# Schematic_pH_CAN.net
KiCad netlist of a schematic drawn in Altium Designer
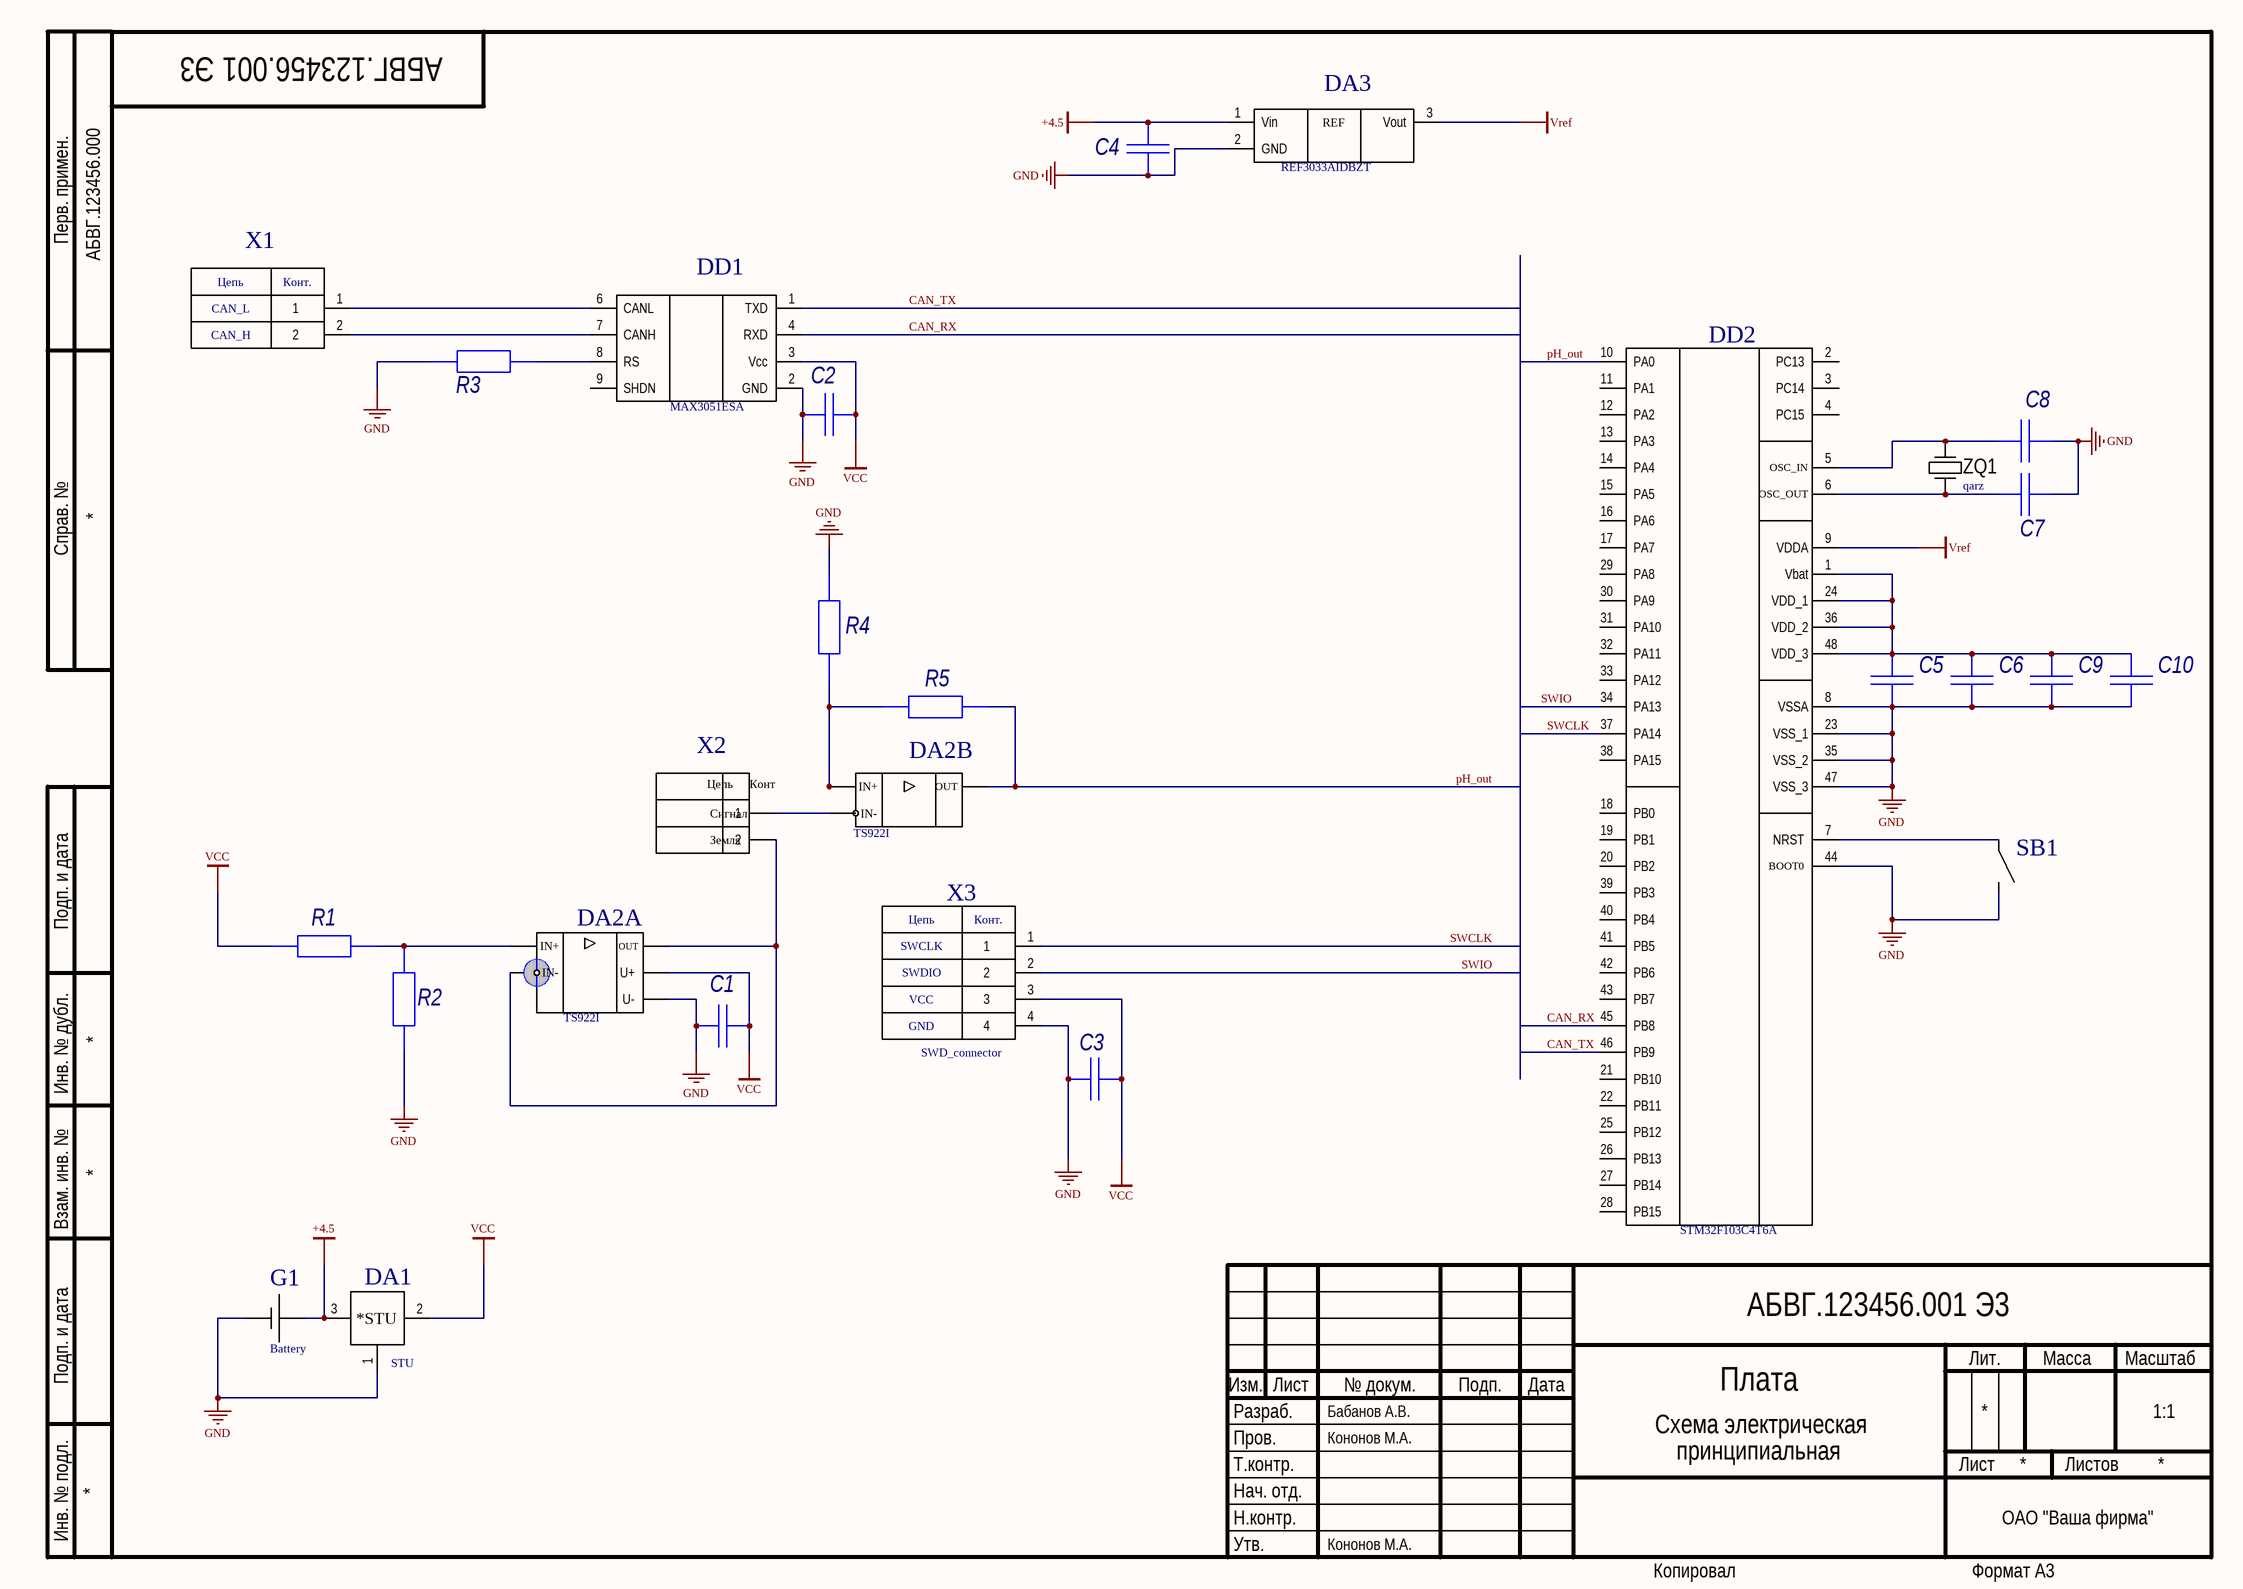
[diagram p0: Schematic_pH_CAN.SchDoc]

(export (version "E")
  (design (tool "Eeschema 10.0.6"))
  (components
    (comp (ref "C1")
      (value "Capacitor")
      (footprint "StandardCase:CAP: 0805")
      (fields (field (name "PUBLISHER") "Andrew Danich"))
      (libsource (lib "Schlib1") (part "Capacitor"))
    )
    (comp (ref "C2")
      (value "Capacitor")
      (footprint "StandardCase:CAP: 0805")
      (fields (field (name "PUBLISHER") "Andrew Danich"))
      (libsource (lib "Schlib1") (part "Capacitor"))
    )
    (comp (ref "C3")
      (value "Capacitor")
      (footprint "StandardCase:CAP: 0805")
      (fields (field (name "PUBLISHER") "Andrew Danich"))
      (libsource (lib "Schlib1") (part "Capacitor"))
    )
    (comp (ref "C4")
      (value "Capacitor")
      (footprint "StandardCase:CAP: 0805")
      (fields (field (name "PUBLISHER") "Andrew Danich"))
      (libsource (lib "Schlib1") (part "Capacitor"))
    )
    (comp (ref "C5")
      (value "Capacitor")
      (footprint "StandardCase:CAP: 0805")
      (fields (field (name "PUBLISHER") "Andrew Danich"))
      (libsource (lib "Schlib1") (part "Capacitor"))
    )
    (comp (ref "C6")
      (value "Capacitor")
      (footprint "StandardCase:CAP: 0805")
      (fields (field (name "PUBLISHER") "Andrew Danich"))
      (libsource (lib "Schlib1") (part "Capacitor"))
    )
    (comp (ref "C7")
      (value "Capacitor")
      (footprint "StandardCase:CAP: 0805")
      (fields (field (name "PUBLISHER") "Andrew Danich"))
      (libsource (lib "Schlib1") (part "Capacitor"))
    )
    (comp (ref "C8")
      (value "Capacitor")
      (footprint "StandardCase:CAP: 0805")
      (fields (field (name "PUBLISHER") "Andrew Danich"))
      (libsource (lib "Schlib1") (part "Capacitor"))
    )
    (comp (ref "C9")
      (value "Capacitor")
      (footprint "StandardCase:CAP: 0805")
      (fields (field (name "PUBLISHER") "Andrew Danich"))
      (libsource (lib "Schlib1") (part "Capacitor"))
    )
    (comp (ref "C10")
      (value "Capacitor")
      (footprint "StandardCase:CAP: 0805")
      (fields (field (name "PUBLISHER") "Andrew Danich"))
      (libsource (lib "Schlib1") (part "Capacitor"))
    )
    (comp (ref "DA1")
      (value "STU")
      (footprint "SOT223")
      (description "Стабилизатор напряжения")
      (libsource (lib "Schlib1") (part "STU"))
    )
    (comp (ref "DA2")
      (value "TS922I")
      (footprint "8-SO")
      (description "OPAMP 2 channel")
      (libsource (lib "Schlib1") (part "TS922I"))
    )
    (comp (ref "DA3")
      (value "REF3033AIDBZT")
      (description "ИОН 3.3 В")
      (libsource (lib "Schlib1") (part "REF3033AIDBZT"))
    )
    (comp (ref "DD1") (value "MAX3051ESA") (libsource (lib "Schlib1") (part "MAX3051ESA")))
    (comp (ref "DD2")
      (value "STM32F103C4T6A")
      (description "МК")
      (libsource (lib "Schlib1") (part "STM32F103C4T6A"))
    )
    (comp (ref "G1") (value "Battery") (footprint "VCC Pad") (libsource (lib "Schlib1") (part "Battery")))
    (comp (ref "R1")
      (value "Resistor")
      (footprint "RES: 0805")
      (fields (field (name "PUBLISHER") "Andrew Danich"))
      (libsource (lib "Schlib1") (part "Resistor"))
    )
    (comp (ref "R2")
      (value "Resistor")
      (footprint "RES: 0805")
      (fields (field (name "PUBLISHER") "Andrew Danich"))
      (libsource (lib "Schlib1") (part "Resistor"))
    )
    (comp (ref "R3")
      (value "Resistor")
      (footprint "RES: 0805")
      (fields (field (name "PUBLISHER") "Andrew Danich"))
      (libsource (lib "Schlib1") (part "Resistor"))
    )
    (comp (ref "R4")
      (value "Resistor")
      (footprint "RES: 0805")
      (fields (field (name "PUBLISHER") "Andrew Danich"))
      (libsource (lib "Schlib1") (part "Resistor"))
    )
    (comp (ref "R5")
      (value "Resistor")
      (footprint "RES: 0805")
      (fields (field (name "PUBLISHER") "Andrew Danich"))
      (libsource (lib "Schlib1") (part "Resistor"))
    )
    (comp (ref "SB1")
      (value "KLS7-TS6601-7")
      (footprint "KLS7-TS6601-7")
      (libsource (lib "Schlib1") (part "KLS7-TS6601-7"))
    )
    (comp (ref "X1")
      (value "CAN_L/CAN_H")
      (footprint "Клеммная колодка")
      (libsource (lib "Schlib1") (part "CAN_L/CAN_H"))
    )
    (comp (ref "X2") (value "BNC") (footprint "BNC") (libsource (lib "Schlib1") (part "BNC")))
    (comp (ref "X3")
      (value "SWD_connector")
      (footprint "PLS-4")
      (libsource (lib "Schlib1") (part "SWD_connector"))
    )
    (comp (ref "ZQ1")
      (value "qarz")
      (footprint "StandardCase:qarz")
      (libsource (lib "Schlib1") (part "qarz"))
    )
  )
  (nets
    (net (code "1") (name "+4.5") (class "Default")
      (node (ref "C4") (pin "2") (pinfunction "2_2") (pintype "passive"))
      (node (ref "DA1") (pin "3") (pinfunction "3_3") (pintype "passive"))
      (node (ref "DA3") (pin "1") (pinfunction "Vin_1") (pintype "passive"))
      (node (ref "G1") (pin "1") (pinfunction "1_1") (pintype "passive"))
    )
    (net (code "2") (name "/CAN_RX") (class "Default")
      (node (ref "DA2") (pin "7") (pinfunction "OUT_7") (pintype "passive"))
      (node (ref "DD1") (pin "4") (pinfunction "RXD_4") (pintype "passive"))
      (node (ref "DD2") (pin "10") (pinfunction "PA0_10") (pintype "passive"))
      (node (ref "DD2") (pin "45") (pinfunction "PB8_45") (pintype "passive"))
      (node (ref "R5") (pin "1") (pinfunction "1_1") (pintype "passive"))
    )
    (net (code "3") (name "/CAN_TX") (class "Default")
      (node (ref "DD1") (pin "1") (pinfunction "TXD_1") (pintype "passive"))
      (node (ref "DD2") (pin "46") (pinfunction "PB9_46") (pintype "passive"))
    )
    (net (code "4") (name "/SWCLK") (class "Default")
      (node (ref "DD2") (pin "37") (pinfunction "PA14_37") (pintype "passive"))
      (node (ref "X3") (pin "1") (pinfunction "1_1") (pintype "passive"))
    )
    (net (code "5") (name "/SWIO") (class "Default")
      (node (ref "DD2") (pin "34") (pinfunction "PA13_34") (pintype "passive"))
      (node (ref "X3") (pin "2") (pinfunction "2_2") (pintype "passive"))
    )
    (net (code "6") (name "GND") (class "Default")
      (node (ref "C1") (pin "2") (pinfunction "2_2") (pintype "passive"))
      (node (ref "C10") (pin "1") (pinfunction "1_1") (pintype "passive"))
      (node (ref "C2") (pin "2") (pinfunction "2_2") (pintype "passive"))
      (node (ref "C3") (pin "2") (pinfunction "2_2") (pintype "passive"))
      (node (ref "C4") (pin "1") (pinfunction "1_1") (pintype "passive"))
      (node (ref "C5") (pin "1") (pinfunction "1_1") (pintype "passive"))
      (node (ref "C6") (pin "1") (pinfunction "1_1") (pintype "passive"))
      (node (ref "C7") (pin "2") (pinfunction "2_2") (pintype "passive"))
      (node (ref "C8") (pin "2") (pinfunction "2_2") (pintype "passive"))
      (node (ref "C9") (pin "1") (pinfunction "1_1") (pintype "passive"))
      (node (ref "DA1") (pin "1") (pinfunction "1_1") (pintype "passive"))
      (node (ref "DA2") (pin "4") (pinfunction "U-_4") (pintype "passive"))
      (node (ref "DA3") (pin "2") (pinfunction "GND_2") (pintype "passive"))
      (node (ref "DD1") (pin "2") (pinfunction "GND_2") (pintype "passive"))
      (node (ref "DD2") (pin "23") (pinfunction "VSS_1_23") (pintype "passive"))
      (node (ref "DD2") (pin "35") (pinfunction "VSS_2_35") (pintype "passive"))
      (node (ref "DD2") (pin "44") (pinfunction "BOOT0_44") (pintype "passive"))
      (node (ref "DD2") (pin "47") (pinfunction "VSS_3_47") (pintype "passive"))
      (node (ref "DD2") (pin "8") (pinfunction "VSSA_8") (pintype "passive"))
      (node (ref "G1") (pin "2") (pinfunction "2_2") (pintype "passive"))
      (node (ref "R2") (pin "1") (pinfunction "1_1") (pintype "passive"))
      (node (ref "R3") (pin "1") (pinfunction "1_1") (pintype "passive"))
      (node (ref "R4") (pin "2") (pinfunction "2_2") (pintype "passive"))
      (node (ref "SB1") (pin "2") (pinfunction "2_2") (pintype "passive"))
      (node (ref "X3") (pin "4") (pinfunction "4_4") (pintype "passive"))
    )
    (net (code "7") (name "Net-(DA2A-IN+)") (class "Default")
      (node (ref "DA2") (pin "3") (pinfunction "IN+_3") (pintype "passive"))
      (node (ref "R1") (pin "2") (pinfunction "2_2") (pintype "passive"))
      (node (ref "R2") (pin "2") (pinfunction "2_2") (pintype "passive"))
    )
    (net (code "8") (name "Net-(DA2A-IN-)") (class "Default")
      (node (ref "DA2") (pin "1") (pinfunction "OUT_1") (pintype "passive"))
      (node (ref "DA2") (pin "2") (pinfunction "IN-_2") (pintype "passive"))
      (node (ref "X2") (pin "2") (pinfunction "2_2") (pintype "passive"))
    )
    (net (code "9") (name "Net-(DA2B-IN+)") (class "Default")
      (node (ref "DA2") (pin "5") (pinfunction "IN+_5") (pintype "passive"))
      (node (ref "R4") (pin "1") (pinfunction "1_1") (pintype "passive"))
      (node (ref "R5") (pin "2") (pinfunction "2_2") (pintype "passive"))
    )
    (net (code "10") (name "Net-(DA2B-IN-)") (class "Default")
      (node (ref "DA2") (pin "6") (pinfunction "IN-_6") (pintype "passive"))
      (node (ref "X2") (pin "1") (pinfunction "1_1") (pintype "passive"))
    )
    (net (code "11") (name "Net-(DD1-CANH)") (class "Default")
      (node (ref "DD1") (pin "7") (pinfunction "CANH_7") (pintype "passive"))
      (node (ref "X1") (pin "2") (pinfunction "2_2") (pintype "passive"))
    )
    (net (code "12") (name "Net-(DD1-CANL)") (class "Default")
      (node (ref "DD1") (pin "6") (pinfunction "CANL_6") (pintype "passive"))
      (node (ref "X1") (pin "1") (pinfunction "1_1") (pintype "passive"))
    )
    (net (code "13") (name "Net-(DD1-RS)") (class "Default")
      (node (ref "DD1") (pin "8") (pinfunction "RS_8") (pintype "passive"))
      (node (ref "R3") (pin "2") (pinfunction "2_2") (pintype "passive"))
    )
    (net (code "14") (name "Net-(DD2-NRST)") (class "Default")
      (node (ref "DD2") (pin "7") (pinfunction "NRST_7") (pintype "passive"))
      (node (ref "SB1") (pin "1") (pinfunction "1_1") (pintype "passive"))
    )
    (net (code "15") (name "Net-(DD2-OSC_IN)") (class "Default")
      (node (ref "C8") (pin "1") (pinfunction "1_1") (pintype "passive"))
      (node (ref "DD2") (pin "5") (pinfunction "OSC_IN_5") (pintype "passive"))
      (node (ref "ZQ1") (pin "2") (pinfunction "2_2") (pintype "passive"))
    )
    (net (code "16") (name "Net-(DD2-OSC_OUT)") (class "Default")
      (node (ref "C7") (pin "1") (pinfunction "1_1") (pintype "passive"))
      (node (ref "DD2") (pin "6") (pinfunction "OSC_OUT_6") (pintype "passive"))
      (node (ref "ZQ1") (pin "1") (pinfunction "1_1") (pintype "passive"))
    )
    (net (code "17") (name "Net-(DD2-VDD_1)") (class "Default")
      (node (ref "C10") (pin "2") (pinfunction "2_2") (pintype "passive"))
      (node (ref "C5") (pin "2") (pinfunction "2_2") (pintype "passive"))
      (node (ref "C6") (pin "2") (pinfunction "2_2") (pintype "passive"))
      (node (ref "C9") (pin "2") (pinfunction "2_2") (pintype "passive"))
      (node (ref "DD2") (pin "1") (pinfunction "Vbat_1") (pintype "passive"))
      (node (ref "DD2") (pin "24") (pinfunction "VDD_1_24") (pintype "passive"))
      (node (ref "DD2") (pin "36") (pinfunction "VDD_2_36") (pintype "passive"))
      (node (ref "DD2") (pin "48") (pinfunction "VDD_3_48") (pintype "passive"))
    )
    (net (code "18") (name "VCC") (class "Default")
      (node (ref "C1") (pin "1") (pinfunction "1_1") (pintype "passive"))
      (node (ref "C2") (pin "1") (pinfunction "1_1") (pintype "passive"))
      (node (ref "C3") (pin "1") (pinfunction "1_1") (pintype "passive"))
      (node (ref "DA1") (pin "2") (pinfunction "2_2") (pintype "passive"))
      (node (ref "DA2") (pin "8") (pinfunction "U+_8") (pintype "passive"))
      (node (ref "DD1") (pin "3") (pinfunction "Vcc_3") (pintype "passive"))
      (node (ref "R1") (pin "1") (pinfunction "1_1") (pintype "passive"))
      (node (ref "X3") (pin "3") (pinfunction "3_3") (pintype "passive"))
    )
    (net (code "19") (name "Vref") (class "Default")
      (node (ref "DA3") (pin "3") (pinfunction "Vout_3") (pintype "passive"))
      (node (ref "DD2") (pin "9") (pinfunction "VDDA_9") (pintype "passive"))
    )
    (net (code "20") (name "unconnected-(DD1-SHDN-Pad9)") (class "Default")
      (node (ref "DD1") (pin "9") (pinfunction "SHDN_9") (pintype "passive"))
    )
    (net (code "21") (name "unconnected-(DD2-PA1-Pad11)") (class "Default")
      (node (ref "DD2") (pin "11") (pinfunction "PA1_11") (pintype "passive"))
    )
    (net (code "22") (name "unconnected-(DD2-PA2-Pad12)") (class "Default")
      (node (ref "DD2") (pin "12") (pinfunction "PA2_12") (pintype "passive"))
    )
    (net (code "23") (name "unconnected-(DD2-PA3-Pad13)") (class "Default")
      (node (ref "DD2") (pin "13") (pinfunction "PA3_13") (pintype "passive"))
    )
    (net (code "24") (name "unconnected-(DD2-PA4-Pad14)") (class "Default")
      (node (ref "DD2") (pin "14") (pinfunction "PA4_14") (pintype "passive"))
    )
    (net (code "25") (name "unconnected-(DD2-PA5-Pad15)") (class "Default")
      (node (ref "DD2") (pin "15") (pinfunction "PA5_15") (pintype "passive"))
    )
    (net (code "26") (name "unconnected-(DD2-PA6-Pad16)") (class "Default")
      (node (ref "DD2") (pin "16") (pinfunction "PA6_16") (pintype "passive"))
    )
    (net (code "27") (name "unconnected-(DD2-PA7-Pad17)") (class "Default")
      (node (ref "DD2") (pin "17") (pinfunction "PA7_17") (pintype "passive"))
    )
    (net (code "28") (name "unconnected-(DD2-PA8-Pad29)") (class "Default")
      (node (ref "DD2") (pin "29") (pinfunction "PA8_29") (pintype "passive"))
    )
    (net (code "29") (name "unconnected-(DD2-PA9-Pad30)") (class "Default")
      (node (ref "DD2") (pin "30") (pinfunction "PA9_30") (pintype "passive"))
    )
    (net (code "30") (name "unconnected-(DD2-PA10-Pad31)") (class "Default")
      (node (ref "DD2") (pin "31") (pinfunction "PA10_31") (pintype "passive"))
    )
    (net (code "31") (name "unconnected-(DD2-PA11-Pad32)") (class "Default")
      (node (ref "DD2") (pin "32") (pinfunction "PA11_32") (pintype "passive"))
    )
    (net (code "32") (name "unconnected-(DD2-PA12-Pad33)") (class "Default")
      (node (ref "DD2") (pin "33") (pinfunction "PA12_33") (pintype "passive"))
    )
    (net (code "33") (name "unconnected-(DD2-PA15-Pad38)") (class "Default")
      (node (ref "DD2") (pin "38") (pinfunction "PA15_38") (pintype "passive"))
    )
    (net (code "34") (name "unconnected-(DD2-PB0-Pad18)") (class "Default")
      (node (ref "DD2") (pin "18") (pinfunction "PB0_18") (pintype "passive"))
    )
    (net (code "35") (name "unconnected-(DD2-PB1-Pad19)") (class "Default")
      (node (ref "DD2") (pin "19") (pinfunction "PB1_19") (pintype "passive"))
    )
    (net (code "36") (name "unconnected-(DD2-PB2-Pad20)") (class "Default")
      (node (ref "DD2") (pin "20") (pinfunction "PB2_20") (pintype "passive"))
    )
    (net (code "37") (name "unconnected-(DD2-PB3-Pad39)") (class "Default")
      (node (ref "DD2") (pin "39") (pinfunction "PB3_39") (pintype "passive"))
    )
    (net (code "38") (name "unconnected-(DD2-PB4-Pad40)") (class "Default")
      (node (ref "DD2") (pin "40") (pinfunction "PB4_40") (pintype "passive"))
    )
    (net (code "39") (name "unconnected-(DD2-PB5-Pad41)") (class "Default")
      (node (ref "DD2") (pin "41") (pinfunction "PB5_41") (pintype "passive"))
    )
    (net (code "40") (name "unconnected-(DD2-PB6-Pad42)") (class "Default")
      (node (ref "DD2") (pin "42") (pinfunction "PB6_42") (pintype "passive"))
    )
    (net (code "41") (name "unconnected-(DD2-PB7-Pad43)") (class "Default")
      (node (ref "DD2") (pin "43") (pinfunction "PB7_43") (pintype "passive"))
    )
    (net (code "42") (name "unconnected-(DD2-PB10-Pad21)") (class "Default")
      (node (ref "DD2") (pin "21") (pinfunction "PB10_21") (pintype "passive"))
    )
    (net (code "43") (name "unconnected-(DD2-PB11-Pad22)") (class "Default")
      (node (ref "DD2") (pin "22") (pinfunction "PB11_22") (pintype "passive"))
    )
    (net (code "44") (name "unconnected-(DD2-PB12-Pad25)") (class "Default")
      (node (ref "DD2") (pin "25") (pinfunction "PB12_25") (pintype "passive"))
    )
    (net (code "45") (name "unconnected-(DD2-PB13-Pad26)") (class "Default")
      (node (ref "DD2") (pin "26") (pinfunction "PB13_26") (pintype "passive"))
    )
    (net (code "46") (name "unconnected-(DD2-PB14-Pad27)") (class "Default")
      (node (ref "DD2") (pin "27") (pinfunction "PB14_27") (pintype "passive"))
    )
    (net (code "47") (name "unconnected-(DD2-PB15-Pad28)") (class "Default")
      (node (ref "DD2") (pin "28") (pinfunction "PB15_28") (pintype "passive"))
    )
    (net (code "48") (name "unconnected-(DD2-PC13-Pad2)") (class "Default")
      (node (ref "DD2") (pin "2") (pinfunction "PC13_2") (pintype "passive"))
    )
    (net (code "49") (name "unconnected-(DD2-PC14-Pad3)") (class "Default")
      (node (ref "DD2") (pin "3") (pinfunction "PC14_3") (pintype "passive"))
    )
    (net (code "50") (name "unconnected-(DD2-PC15-Pad4)") (class "Default")
      (node (ref "DD2") (pin "4") (pinfunction "PC15_4") (pintype "passive"))
    )
  )
)
